# gatormicrophone.net
KiCad netlist of a schematic drawn in EAGLE
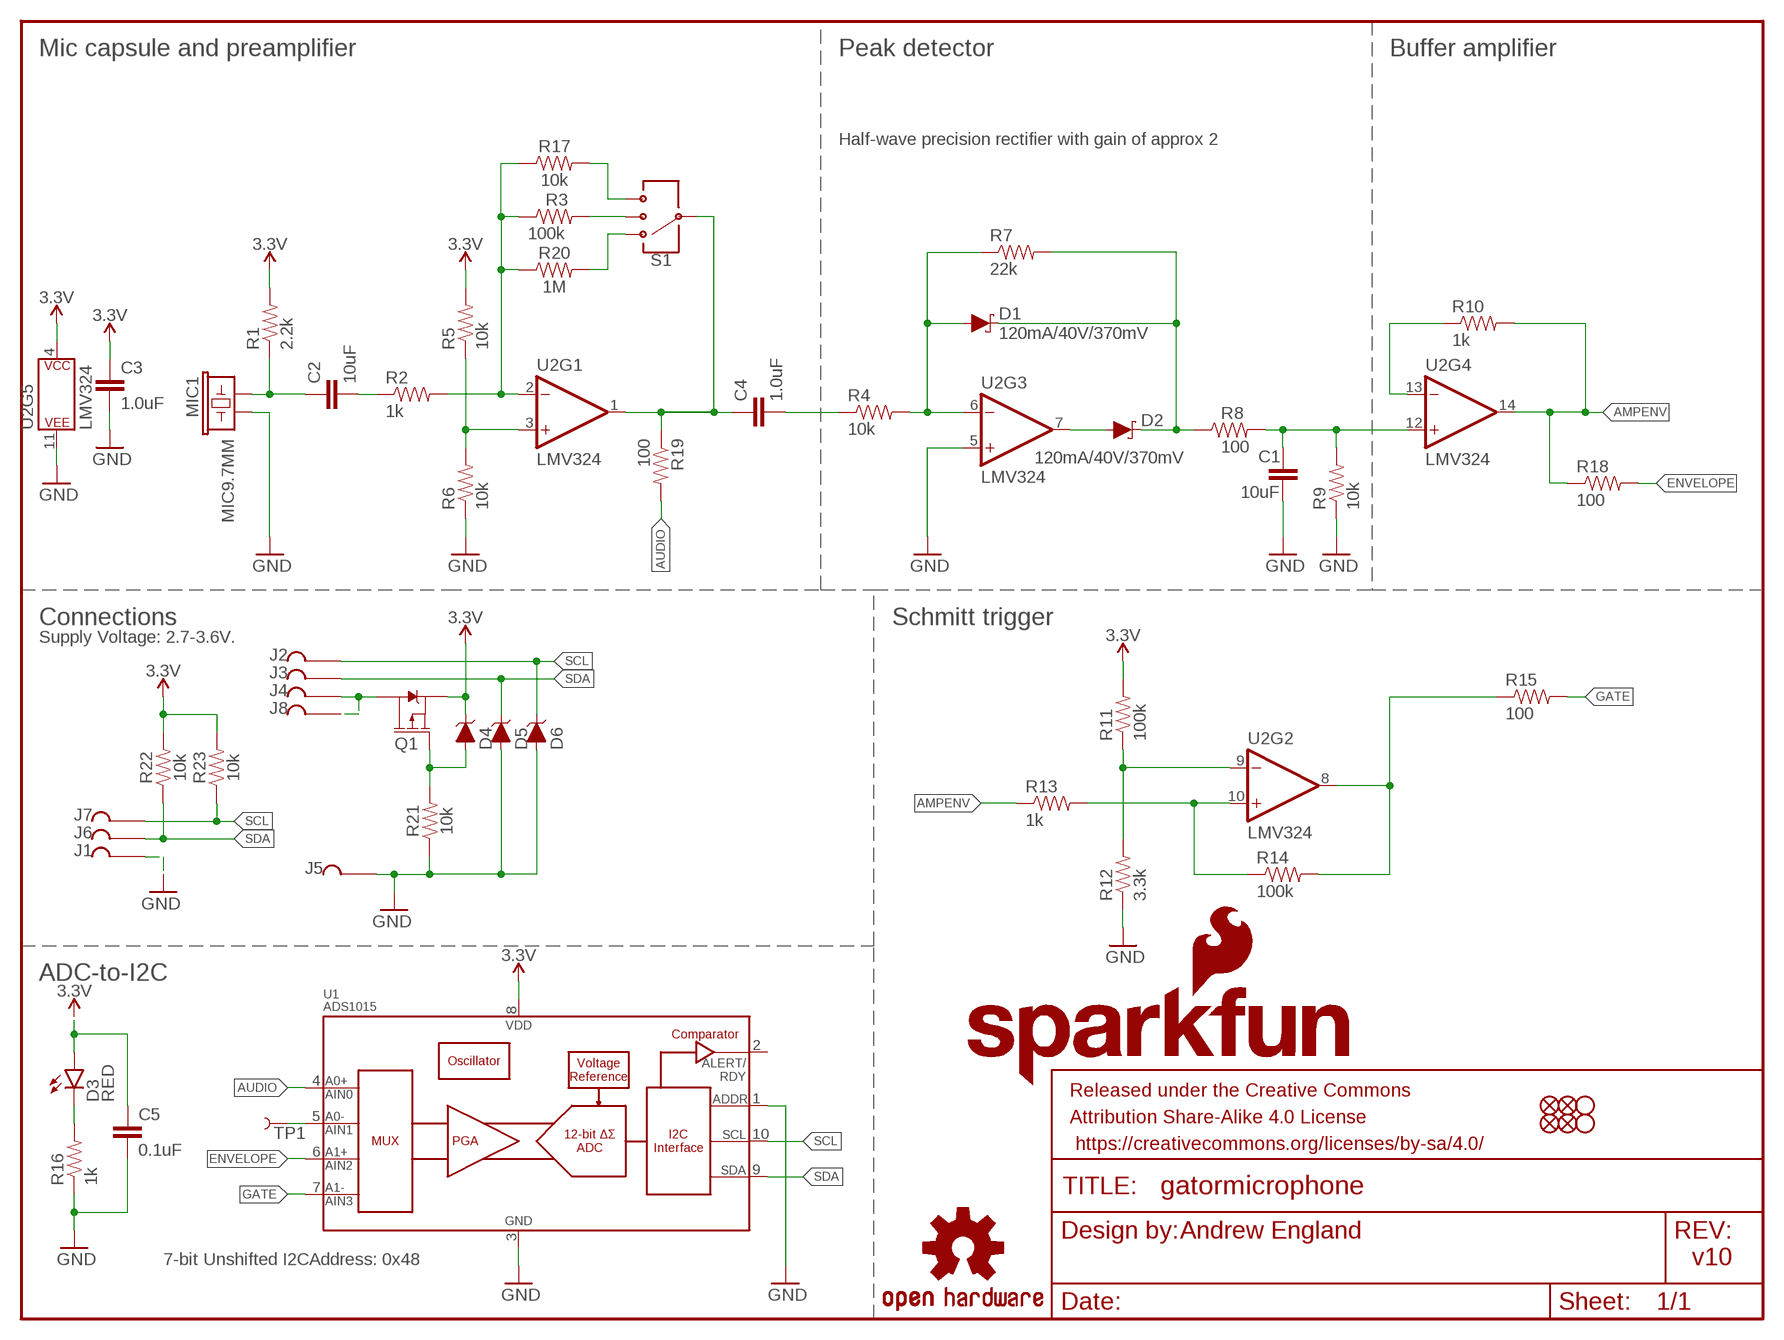
[diagram p0: schematic, sheet 1]

(export (version "E")
  (design (tool "Eeschema 10.0.6"))
  (components
    (comp (ref "C1")
      (value "10uF")
      (footprint "eagle-import:1206@1")
      (libsource (lib "eagle-import") (part "10UF-6.3V-20%(1206)"))
    )
    (comp (ref "C2")
      (value "10uF")
      (footprint "eagle-import:1206@1")
      (libsource (lib "eagle-import") (part "10UF-6.3V-20%(1206)"))
    )
    (comp (ref "C3")
      (value "1.0uF")
      (footprint "eagle-import:0603")
      (libsource (lib "eagle-import") (part "1.0UF-0603-16V-10%"))
    )
    (comp (ref "C4")
      (value "1.0uF")
      (footprint "eagle-import:0603")
      (libsource (lib "eagle-import") (part "1.0UF-0603-16V-10%"))
    )
    (comp (ref "C5")
      (value "0.1uF")
      (footprint "eagle-import:0603")
      (libsource (lib "eagle-import") (part "0.1UF-0603-25V-(+80/-20%)"))
    )
    (comp (ref "D1")
      (value "120mA/40V/370mV")
      (footprint "eagle-import:SOD-523")
      (libsource (lib "eagle-import") (part "DIODE-SCHOTTKY-RB751S40"))
    )
    (comp (ref "D2")
      (value "120mA/40V/370mV")
      (footprint "eagle-import:SOD-523")
      (libsource (lib "eagle-import") (part "DIODE-SCHOTTKY-RB751S40"))
    )
    (comp (ref "D3")
      (value "RED")
      (footprint "eagle-import:LED-0603")
      (libsource (lib "eagle-import") (part "LED-RED0603"))
    )
    (comp (ref "D4")
      (value "3.6V")
      (footprint "eagle-import:SOD-323")
      (libsource (lib "eagle-import") (part "DIODE-ZENER-BZT52C3V6S"))
    )
    (comp (ref "D5")
      (value "3.6V")
      (footprint "eagle-import:SOD-323")
      (libsource (lib "eagle-import") (part "DIODE-ZENER-BZT52C3V6S"))
    )
    (comp (ref "D6")
      (value "3.6V")
      (footprint "eagle-import:SOD-323")
      (libsource (lib "eagle-import") (part "DIODE-ZENER-BZT52C3V6S"))
    )
    (comp (ref "FID1")
      (value "FIDUCIAL1X2")
      (footprint "eagle-import:FIDUCIAL-1X2")
      (libsource (lib "eagle-import") (part "FIDUCIAL1X2"))
    )
    (comp (ref "FID2")
      (value "FIDUCIAL1X2")
      (footprint "eagle-import:FIDUCIAL-1X2")
      (libsource (lib "eagle-import") (part "FIDUCIAL1X2"))
    )
    (comp (ref "FID3")
      (value "FIDUCIAL1X2")
      (footprint "eagle-import:FIDUCIAL-1X2")
      (libsource (lib "eagle-import") (part "FIDUCIAL1X2"))
    )
    (comp (ref "FID4")
      (value "FIDUCIAL1X2")
      (footprint "eagle-import:FIDUCIAL-1X2")
      (libsource (lib "eagle-import") (part "FIDUCIAL1X2"))
    )
    (comp (ref "FRAME1")
      (value "FRAME-LETTER")
      (footprint "eagle-import:CREATIVE_COMMONS")
      (libsource (lib "eagle-import") (part "FRAME-LETTER"))
    )
    (comp (ref "H1")
      (value "STAND-OFFTIGHT")
      (footprint "eagle-import:STAND-OFF-TIGHT")
      (libsource (lib "eagle-import") (part "STAND-OFFTIGHT"))
    )
    (comp (ref "H2")
      (value "STAND-OFFTIGHT")
      (footprint "eagle-import:STAND-OFF-TIGHT")
      (libsource (lib "eagle-import") (part "STAND-OFFTIGHT"))
    )
    (comp (ref "J1")
      (value "GATORGATOR_MINI")
      (footprint "eagle-import:GATOR_MINI")
      (libsource (lib "eagle-import") (part "GATORGATOR_MINI"))
    )
    (comp (ref "J2")
      (value "GATORGATOR_MINI")
      (footprint "eagle-import:GATOR_MINI")
      (libsource (lib "eagle-import") (part "GATORGATOR_MINI"))
    )
    (comp (ref "J3")
      (value "GATORGATOR_MINI")
      (footprint "eagle-import:GATOR_MINI")
      (libsource (lib "eagle-import") (part "GATORGATOR_MINI"))
    )
    (comp (ref "J4")
      (value "GATORGATOR_MINI")
      (footprint "eagle-import:GATOR_MINI")
      (libsource (lib "eagle-import") (part "GATORGATOR_MINI"))
    )
    (comp (ref "J5")
      (value "GATORGATOR_MINI")
      (footprint "eagle-import:GATOR_MINI")
      (libsource (lib "eagle-import") (part "GATORGATOR_MINI"))
    )
    (comp (ref "J6")
      (value "GATORGATOR_MINI")
      (footprint "eagle-import:GATOR_MINI")
      (libsource (lib "eagle-import") (part "GATORGATOR_MINI"))
    )
    (comp (ref "J7")
      (value "GATORGATOR_MINI")
      (footprint "eagle-import:GATOR_MINI")
      (libsource (lib "eagle-import") (part "GATORGATOR_MINI"))
    )
    (comp (ref "J8")
      (value "GATORGATOR_MINI")
      (footprint "eagle-import:GATOR_MINI")
      (libsource (lib "eagle-import") (part "GATORGATOR_MINI"))
    )
    (comp (ref "LOGO1")
      (value "OSHW-LOGOS")
      (footprint "eagle-import:OSHW-LOGO-S")
      (libsource (lib "eagle-import") (part "OSHW-LOGOS"))
    )
    (comp (ref "LOGO2")
      (value "SFE_LOGO_NAME_FLAME.2_INCH")
      (footprint "eagle-import:SFE_LOGO_NAME_FLAME_.2")
      (libsource (lib "eagle-import") (part "SFE_LOGO_NAME_FLAME.2_INCH"))
    )
    (comp (ref "LOGO3")
      (value "SFE_LOGO_FLAME.2_INCH")
      (footprint "eagle-import:SFE_LOGO_FLAME_.2")
      (libsource (lib "eagle-import") (part "SFE_LOGO_FLAME.2_INCH"))
    )
    (comp (ref "MIC1")
      (value "MIC9.7MM")
      (footprint "eagle-import:MIC-9.7MM")
      (libsource (lib "eagle-import") (part "MIC9.7MM"))
    )
    (comp (ref "Q1")
      (value "2.5A/30V/105mΩ")
      (footprint "eagle-import:SOT23-3")
      (libsource (lib "eagle-import") (part "MOSFET_PCH-DMG2307L"))
    )
    (comp (ref "R1")
      (value "2.2k")
      (footprint "eagle-import:0603")
      (libsource (lib "eagle-import") (part "2.2KOHM-0603-1/10W-1%"))
    )
    (comp (ref "R2")
      (value "1k")
      (footprint "eagle-import:0603")
      (libsource (lib "eagle-import") (part "1KOHM-0603-1/10W-1%"))
    )
    (comp (ref "R3")
      (value "100k")
      (footprint "eagle-import:0603")
      (libsource (lib "eagle-import") (part "100KOHM-0603-1/10W-1%"))
    )
    (comp (ref "R4")
      (value "10k")
      (footprint "eagle-import:0603")
      (libsource (lib "eagle-import") (part "10KOHM-0603-1/10W-1%"))
    )
    (comp (ref "R5")
      (value "10k")
      (footprint "eagle-import:0603")
      (libsource (lib "eagle-import") (part "10KOHM-0603-1/10W-1%"))
    )
    (comp (ref "R6")
      (value "10k")
      (footprint "eagle-import:0603")
      (libsource (lib "eagle-import") (part "10KOHM-0603-1/10W-1%"))
    )
    (comp (ref "R7")
      (value "22k")
      (footprint "eagle-import:0603")
      (libsource (lib "eagle-import") (part "22KOHM-0603-1/10W-1%"))
    )
    (comp (ref "R8")
      (value "100")
      (footprint "eagle-import:0603")
      (libsource (lib "eagle-import") (part "100OHM-0603-1/10W-1%"))
    )
    (comp (ref "R9")
      (value "10k")
      (footprint "eagle-import:0603")
      (libsource (lib "eagle-import") (part "10KOHM-0603-1/10W-1%"))
    )
    (comp (ref "R10")
      (value "1k")
      (footprint "eagle-import:0603")
      (libsource (lib "eagle-import") (part "1KOHM-0603-1/10W-1%"))
    )
    (comp (ref "R11")
      (value "100k")
      (footprint "eagle-import:0603")
      (libsource (lib "eagle-import") (part "100KOHM-0603-1/10W-1%"))
    )
    (comp (ref "R12")
      (value "3.3k")
      (footprint "eagle-import:0603")
      (libsource (lib "eagle-import") (part "3.3KOHM-0603-1/10W-1%"))
    )
    (comp (ref "R13")
      (value "1k")
      (footprint "eagle-import:0603")
      (libsource (lib "eagle-import") (part "1KOHM-0603-1/10W-1%"))
    )
    (comp (ref "R14")
      (value "100k")
      (footprint "eagle-import:0603")
      (libsource (lib "eagle-import") (part "100KOHM-0603-1/10W-1%"))
    )
    (comp (ref "R15")
      (value "100")
      (footprint "eagle-import:0603")
      (libsource (lib "eagle-import") (part "100OHM-0603-1/10W-1%"))
    )
    (comp (ref "R16")
      (value "1k")
      (footprint "eagle-import:0603")
      (libsource (lib "eagle-import") (part "1KOHM-0603-1/10W-1%"))
    )
    (comp (ref "R17")
      (value "10k")
      (footprint "eagle-import:0603")
      (libsource (lib "eagle-import") (part "10KOHM-0603-1/10W-1%"))
    )
    (comp (ref "R18")
      (value "100")
      (footprint "eagle-import:0603")
      (libsource (lib "eagle-import") (part "100OHM-0603-1/10W-1%"))
    )
    (comp (ref "R19")
      (value "100")
      (footprint "eagle-import:0603")
      (libsource (lib "eagle-import") (part "100OHM-0603-1/10W-1%"))
    )
    (comp (ref "R20")
      (value "1M")
      (footprint "eagle-import:0603")
      (libsource (lib "eagle-import") (part "1MOHM-0603-1/4W-5%"))
    )
    (comp (ref "R21")
      (value "10k")
      (footprint "eagle-import:0603")
      (libsource (lib "eagle-import") (part "10KOHM-0603-1/10W-1%"))
    )
    (comp (ref "R22")
      (value "10k")
      (footprint "eagle-import:0603")
      (libsource (lib "eagle-import") (part "10KOHM-0603-1/10W-1%"))
    )
    (comp (ref "R23")
      (value "10k")
      (footprint "eagle-import:0603")
      (libsource (lib "eagle-import") (part "10KOHM-0603-1/10W-1%"))
    )
    (comp (ref "S1")
      (value "SWITCH-SP3T-SMD")
      (footprint "eagle-import:SWITCH_SP3T_SMD")
      (libsource (lib "eagle-import") (part "SWITCH-SP3T-SMD"))
    )
    (comp (ref "TP1")
      (value "TEST-POINT3")
      (footprint "eagle-import:PAD.03X.03")
      (libsource (lib "eagle-import") (part "TEST-POINT3"))
    )
    (comp (ref "U1")
      (value "ADS1015")
      (footprint "eagle-import:MSOP10")
      (libsource (lib "eagle-import") (part "ADS1015"))
    )
    (comp (ref "U2")
      (value "LMV324")
      (footprint "eagle-import:SO14")
      (libsource (lib "eagle-import") (part "LMV324"))
    )
  )
  (nets
    (net (code "1") (name "3.3V") (class "Default")
      (node (ref "C3") (pin "1") (pinfunction "1_1") (pintype "passive"))
      (node (ref "C5") (pin "1") (pinfunction "1_1") (pintype "passive"))
      (node (ref "D3") (pin "A") (pinfunction "A_A") (pintype "passive"))
      (node (ref "D4") (pin "C") (pinfunction "C_C") (pintype "passive"))
      (node (ref "Q1") (pin "2") (pinfunction "S_2") (pintype "bidirectional"))
      (node (ref "R1") (pin "2") (pinfunction "2_2") (pintype "passive"))
      (node (ref "R11") (pin "2") (pinfunction "2_2") (pintype "passive"))
      (node (ref "R22") (pin "2") (pinfunction "2_2") (pintype "passive"))
      (node (ref "R23") (pin "2") (pinfunction "2_2") (pintype "passive"))
      (node (ref "R5") (pin "2") (pinfunction "2_2") (pintype "passive"))
      (node (ref "U1") (pin "8") (pinfunction "VDD_8") (pintype "bidirectional"))
      (node (ref "U2") (pin "4") (pinfunction "P$V+_4") (pintype "bidirectional"))
    )
    (net (code "2") (name "AMPENV") (class "Default")
      (node (ref "R10") (pin "2") (pinfunction "2_2") (pintype "passive"))
      (node (ref "R13") (pin "1") (pinfunction "1_1") (pintype "passive"))
      (node (ref "R18") (pin "1") (pinfunction "1_1") (pintype "passive"))
      (node (ref "U2") (pin "14") (pinfunction "OUT_14") (pintype "output"))
    )
    (net (code "3") (name "AUDIO") (class "Default")
      (node (ref "R19") (pin "2") (pinfunction "2_2") (pintype "passive"))
      (node (ref "U1") (pin "4") (pinfunction "AIN0_4") (pintype "bidirectional"))
    )
    (net (code "4") (name "ENVELOPE") (class "Default")
      (node (ref "R18") (pin "2") (pinfunction "2_2") (pintype "passive"))
      (node (ref "U1") (pin "6") (pinfunction "AIN2_6") (pintype "bidirectional"))
    )
    (net (code "5") (name "GATE") (class "Default")
      (node (ref "R15") (pin "2") (pinfunction "2_2") (pintype "passive"))
      (node (ref "U1") (pin "7") (pinfunction "AIN3_7") (pintype "bidirectional"))
    )
    (net (code "6") (name "GND") (class "Default")
      (node (ref "C1") (pin "2") (pinfunction "2_2") (pintype "passive"))
      (node (ref "C3") (pin "2") (pinfunction "2_2") (pintype "passive"))
      (node (ref "C5") (pin "2") (pinfunction "2_2") (pintype "passive"))
      (node (ref "D5") (pin "A") (pinfunction "A_A") (pintype "passive"))
      (node (ref "D6") (pin "A") (pinfunction "A_A") (pintype "passive"))
      (node (ref "J1") (pin "P$2") (pinfunction "P$1_P$2") (pintype "bidirectional"))
      (node (ref "J5") (pin "P$2") (pinfunction "P$1_P$2") (pintype "bidirectional"))
      (node (ref "MIC1") (pin "2") (pinfunction "2_2") (pintype "passive"))
      (node (ref "R12") (pin "1") (pinfunction "1_1") (pintype "passive"))
      (node (ref "R16") (pin "1") (pinfunction "1_1") (pintype "passive"))
      (node (ref "R21") (pin "1") (pinfunction "1_1") (pintype "passive"))
      (node (ref "R6") (pin "1") (pinfunction "1_1") (pintype "passive"))
      (node (ref "R9") (pin "1") (pinfunction "1_1") (pintype "passive"))
      (node (ref "U1") (pin "1") (pinfunction "ADDR_1") (pintype "bidirectional"))
      (node (ref "U1") (pin "3") (pinfunction "VSS_3") (pintype "bidirectional"))
      (node (ref "U2") (pin "11") (pinfunction "P$V-_11") (pintype "bidirectional"))
      (node (ref "U2") (pin "5") (pinfunction "+IN_5") (pintype "input"))
    )
    (net (code "7") (name "Net-(C2-Pad1)") (class "Default")
      (node (ref "C2") (pin "1") (pinfunction "1_1") (pintype "passive"))
      (node (ref "MIC1") (pin "1") (pinfunction "1_1") (pintype "passive"))
      (node (ref "R1") (pin "1") (pinfunction "1_1") (pintype "passive"))
    )
    (net (code "8") (name "Net-(C2-Pad2)") (class "Default")
      (node (ref "C2") (pin "2") (pinfunction "2_2") (pintype "passive"))
      (node (ref "R2") (pin "1") (pinfunction "1_1") (pintype "passive"))
    )
    (net (code "9") (name "Net-(C4-Pad2)") (class "Default")
      (node (ref "C4") (pin "2") (pinfunction "2_2") (pintype "passive"))
      (node (ref "R4") (pin "1") (pinfunction "1_1") (pintype "passive"))
    )
    (net (code "10") (name "Net-(D1-PadC)") (class "Default")
      (node (ref "D1") (pin "C") (pinfunction "C_C") (pintype "passive"))
      (node (ref "D2") (pin "C") (pinfunction "C_C") (pintype "passive"))
      (node (ref "R7") (pin "2") (pinfunction "2_2") (pintype "passive"))
      (node (ref "R8") (pin "1") (pinfunction "1_1") (pintype "passive"))
    )
    (net (code "11") (name "Net-(D3-PadC)") (class "Default")
      (node (ref "D3") (pin "C") (pinfunction "C_C") (pintype "passive"))
      (node (ref "R16") (pin "2") (pinfunction "2_2") (pintype "passive"))
    )
    (net (code "12") (name "Net-(J4-P$1)") (class "Default")
      (node (ref "J4") (pin "P$2") (pinfunction "P$1_P$2") (pintype "bidirectional"))
      (node (ref "J8") (pin "P$2") (pinfunction "P$1_P$2") (pintype "bidirectional"))
      (node (ref "Q1") (pin "3") (pinfunction "D_3") (pintype "bidirectional"))
    )
    (net (code "13") (name "Net-(Q1-G)") (class "Default")
      (node (ref "D4") (pin "A") (pinfunction "A_A") (pintype "passive"))
      (node (ref "Q1") (pin "1") (pinfunction "G_1") (pintype "bidirectional"))
      (node (ref "R21") (pin "2") (pinfunction "2_2") (pintype "passive"))
    )
    (net (code "14") (name "Net-(R3-Pad2)") (class "Default")
      (node (ref "R3") (pin "2") (pinfunction "2_2") (pintype "passive"))
      (node (ref "S1") (pin "2") (pinfunction "2_2") (pintype "bidirectional"))
    )
    (net (code "15") (name "Net-(R17-Pad2)") (class "Default")
      (node (ref "R17") (pin "2") (pinfunction "2_2") (pintype "passive"))
      (node (ref "S1") (pin "4") (pinfunction "4_4") (pintype "bidirectional"))
    )
    (net (code "16") (name "Net-(R20-Pad2)") (class "Default")
      (node (ref "R20") (pin "2") (pinfunction "2_2") (pintype "passive"))
      (node (ref "S1") (pin "1") (pinfunction "1_1") (pintype "bidirectional"))
    )
    (net (code "17") (name "Net-(TP1-1)") (class "Default")
      (node (ref "TP1") (pin "P$1") (pinfunction "1_P$1") (pintype "bidirectional"))
      (node (ref "U1") (pin "5") (pinfunction "AIN1_5") (pintype "bidirectional"))
    )
    (net (code "18") (name "Net-(U2A-+IN)") (class "Default")
      (node (ref "R5") (pin "1") (pinfunction "1_1") (pintype "passive"))
      (node (ref "R6") (pin "2") (pinfunction "2_2") (pintype "passive"))
      (node (ref "U2") (pin "3") (pinfunction "+IN_3") (pintype "input"))
    )
    (net (code "19") (name "Net-(U2A--IN)") (class "Default")
      (node (ref "R17") (pin "1") (pinfunction "1_1") (pintype "passive"))
      (node (ref "R2") (pin "2") (pinfunction "2_2") (pintype "passive"))
      (node (ref "R20") (pin "1") (pinfunction "1_1") (pintype "passive"))
      (node (ref "R3") (pin "1") (pinfunction "1_1") (pintype "passive"))
      (node (ref "U2") (pin "2") (pinfunction "-IN_2") (pintype "input"))
    )
    (net (code "20") (name "Net-(U2A-OUT)") (class "Default")
      (node (ref "C4") (pin "1") (pinfunction "1_1") (pintype "passive"))
      (node (ref "R19") (pin "1") (pinfunction "1_1") (pintype "passive"))
      (node (ref "S1") (pin "3") (pinfunction "3_3") (pintype "bidirectional"))
      (node (ref "U2") (pin "1") (pinfunction "OUT_1") (pintype "output"))
    )
    (net (code "21") (name "Net-(U2B-+IN)") (class "Default")
      (node (ref "R13") (pin "2") (pinfunction "2_2") (pintype "passive"))
      (node (ref "R14") (pin "1") (pinfunction "1_1") (pintype "passive"))
      (node (ref "U2") (pin "10") (pinfunction "+IN_10") (pintype "input"))
    )
    (net (code "22") (name "Net-(U2B--IN)") (class "Default")
      (node (ref "R11") (pin "1") (pinfunction "1_1") (pintype "passive"))
      (node (ref "R12") (pin "2") (pinfunction "2_2") (pintype "passive"))
      (node (ref "U2") (pin "9") (pinfunction "-IN_9") (pintype "input"))
    )
    (net (code "23") (name "Net-(U2B-OUT)") (class "Default")
      (node (ref "R14") (pin "2") (pinfunction "2_2") (pintype "passive"))
      (node (ref "R15") (pin "1") (pinfunction "1_1") (pintype "passive"))
      (node (ref "U2") (pin "8") (pinfunction "OUT_8") (pintype "output"))
    )
    (net (code "24") (name "Net-(U2C--IN)") (class "Default")
      (node (ref "D1") (pin "A") (pinfunction "A_A") (pintype "passive"))
      (node (ref "R4") (pin "2") (pinfunction "2_2") (pintype "passive"))
      (node (ref "R7") (pin "1") (pinfunction "1_1") (pintype "passive"))
      (node (ref "U2") (pin "6") (pinfunction "-IN_6") (pintype "input"))
    )
    (net (code "25") (name "Net-(U2C-OUT)") (class "Default")
      (node (ref "D2") (pin "A") (pinfunction "A_A") (pintype "passive"))
      (node (ref "U2") (pin "7") (pinfunction "OUT_7") (pintype "output"))
    )
    (net (code "26") (name "Net-(U2D-+IN)") (class "Default")
      (node (ref "C1") (pin "1") (pinfunction "1_1") (pintype "passive"))
      (node (ref "R8") (pin "2") (pinfunction "2_2") (pintype "passive"))
      (node (ref "R9") (pin "2") (pinfunction "2_2") (pintype "passive"))
      (node (ref "U2") (pin "12") (pinfunction "+IN_12") (pintype "input"))
    )
    (net (code "27") (name "Net-(U2D--IN)") (class "Default")
      (node (ref "R10") (pin "1") (pinfunction "1_1") (pintype "passive"))
      (node (ref "U2") (pin "13") (pinfunction "-IN_13") (pintype "input"))
    )
    (net (code "28") (name "SCL") (class "Default")
      (node (ref "D6") (pin "C") (pinfunction "C_C") (pintype "passive"))
      (node (ref "J2") (pin "P$2") (pinfunction "P$1_P$2") (pintype "bidirectional"))
      (node (ref "J7") (pin "P$2") (pinfunction "P$1_P$2") (pintype "bidirectional"))
      (node (ref "R23") (pin "1") (pinfunction "1_1") (pintype "passive"))
      (node (ref "U1") (pin "10") (pinfunction "SCL_10") (pintype "bidirectional"))
    )
    (net (code "29") (name "SDA") (class "Default")
      (node (ref "D5") (pin "C") (pinfunction "C_C") (pintype "passive"))
      (node (ref "J3") (pin "P$2") (pinfunction "P$1_P$2") (pintype "bidirectional"))
      (node (ref "J6") (pin "P$2") (pinfunction "P$1_P$2") (pintype "bidirectional"))
      (node (ref "R22") (pin "1") (pinfunction "1_1") (pintype "passive"))
      (node (ref "U1") (pin "9") (pinfunction "SDA_9") (pintype "bidirectional"))
    )
    (net (code "30") (name "unconnected-(U1-ALERT{slash}RDY-Pad2)") (class "Default")
      (node (ref "U1") (pin "2") (pinfunction "ALERT/RDY_2") (pintype "bidirectional"))
    )
  )
)
